# mb_1d.net
KiCad netlist of a schematic drawn in EAGLE
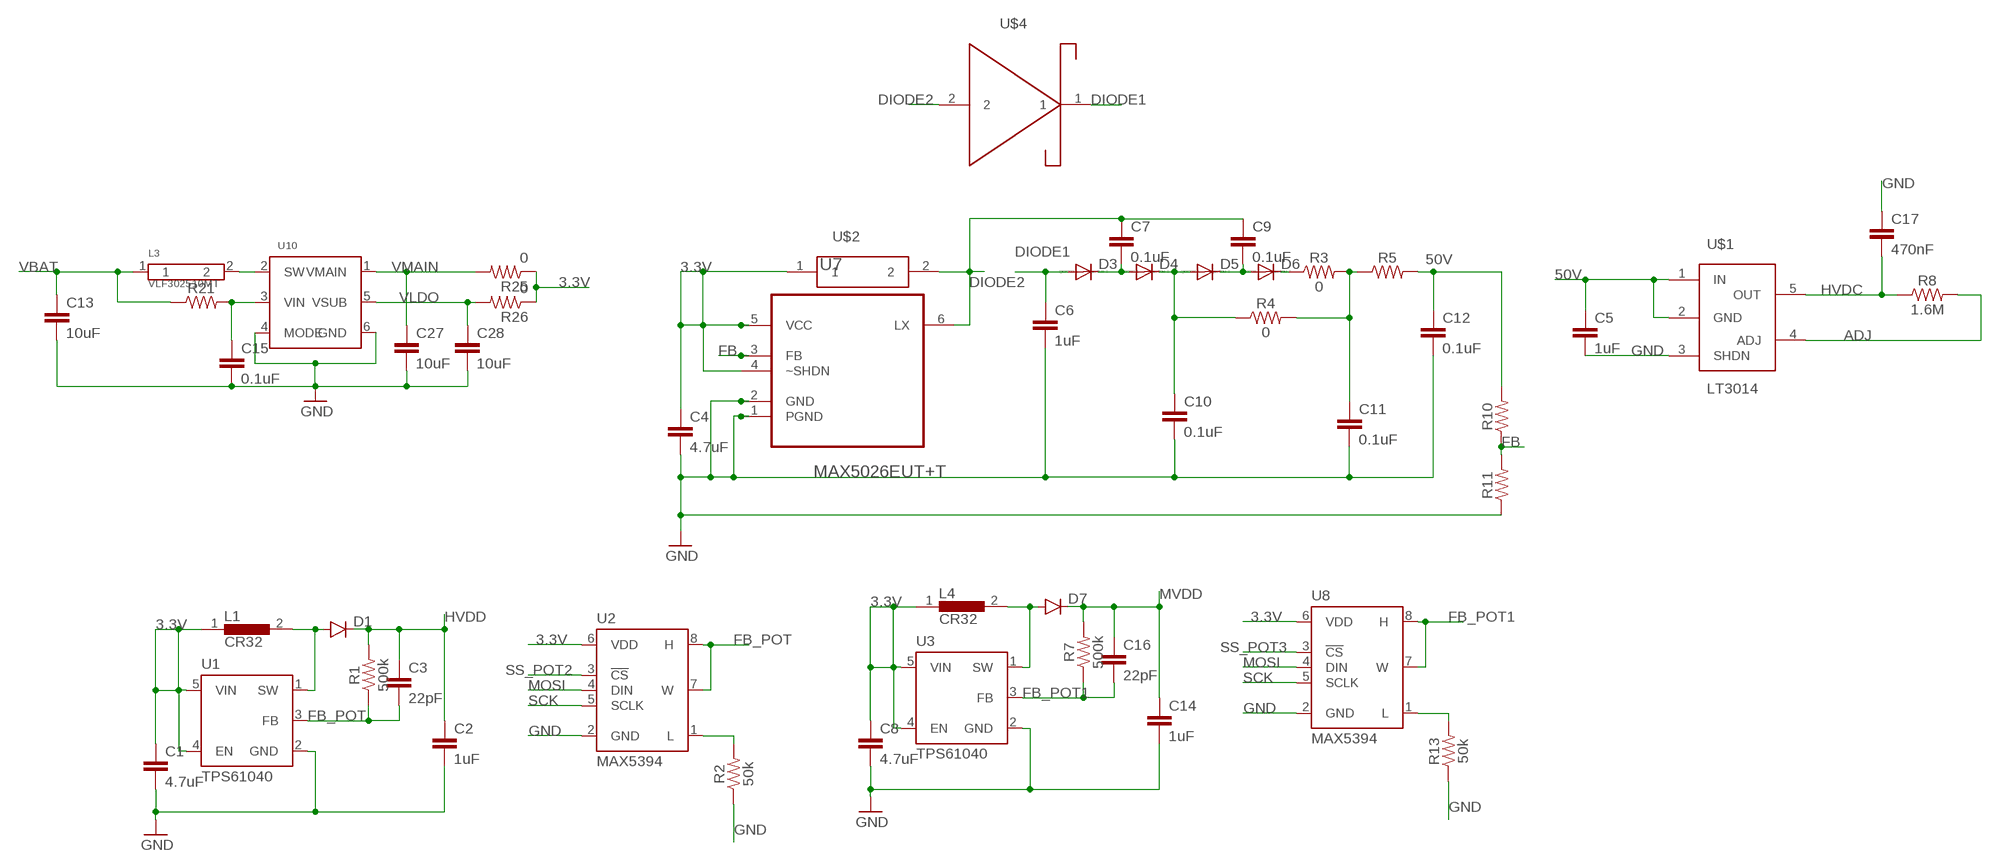
[diagram p0: schematic, sheet 1, part 1 of 2]
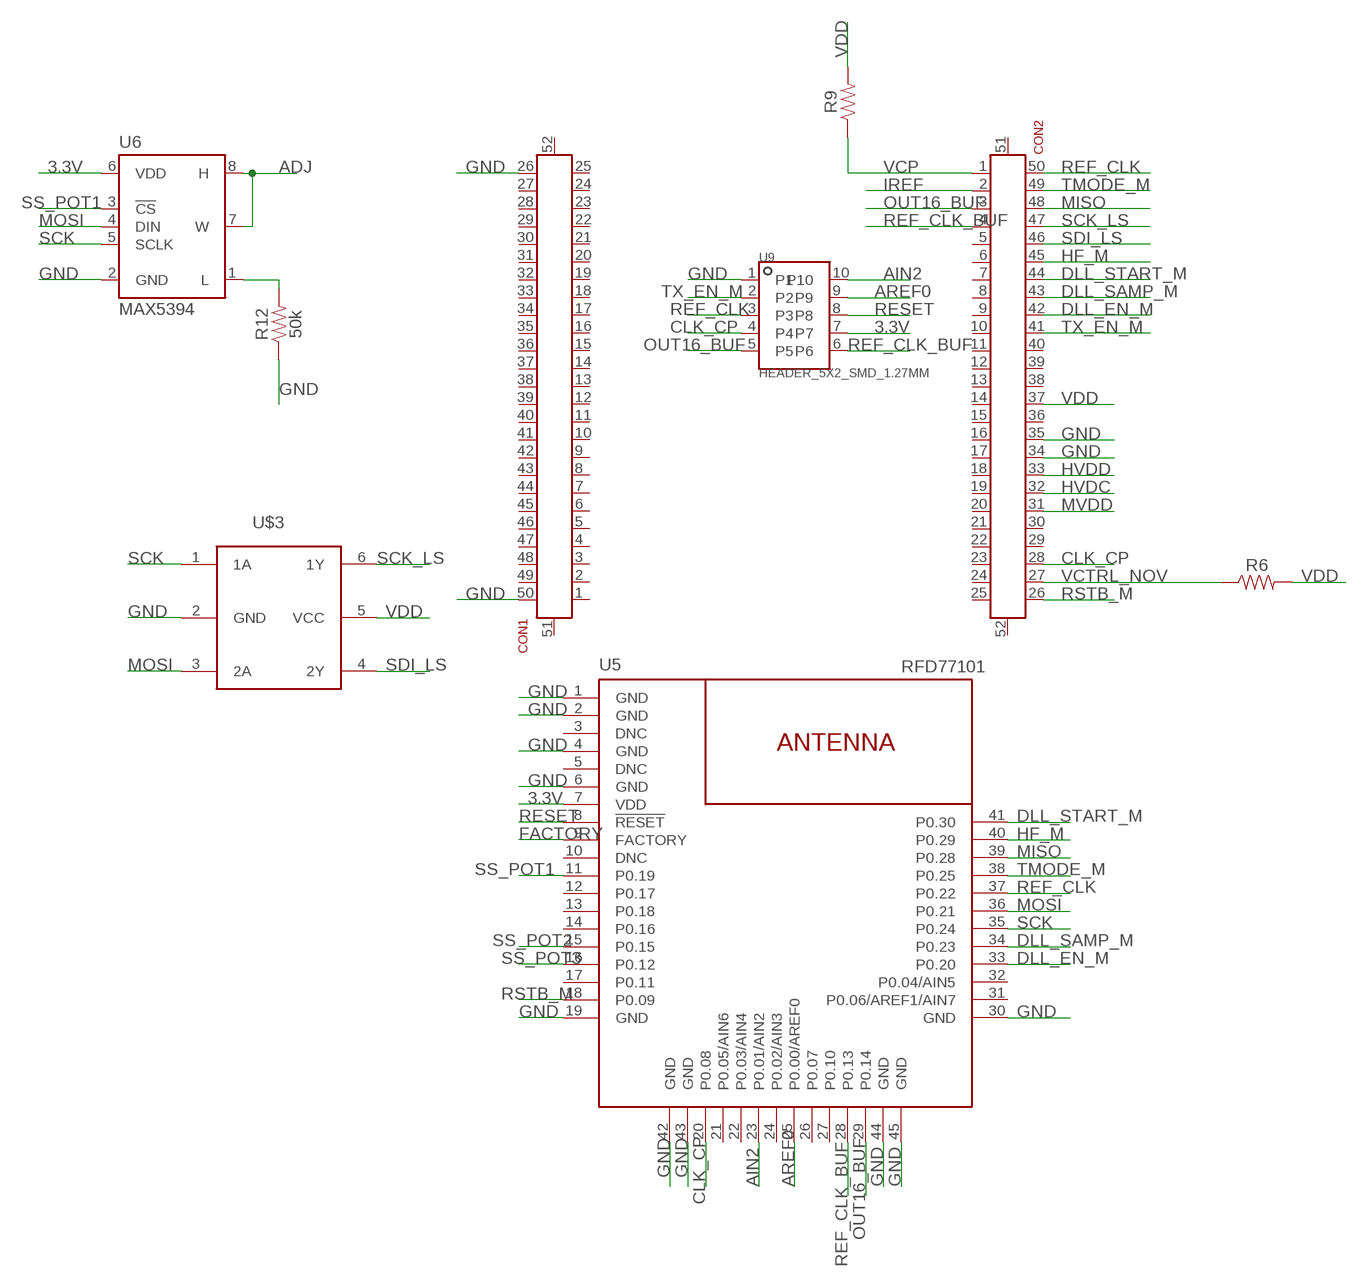
[diagram p1: schematic, sheet 1, part 2 of 2]

(export (version "E")
  (design (tool "Eeschema 10.0.6"))
  (components
    (comp (ref "C1")
      (value "4.7uF")
      (footprint "eagle-import:0805-CAP")
      (libsource (lib "eagle-import") (part "1.0UF-25V-+80/-20(0805){dblquote}"))
    )
    (comp (ref "C2")
      (value "1uF")
      (footprint "eagle-import:1206-CAP")
      (libsource (lib "eagle-import") (part "4.7UF-16V-20%,+80%-(1206)"))
    )
    (comp (ref "C3")
      (value "22pF")
      (footprint "eagle-import:0603-CAP")
      (libsource (lib "eagle-import") (part "22PF-50V-5%(0603)"))
    )
    (comp (ref "C4")
      (value "4.7uF")
      (footprint "eagle-import:0805-CAP")
      (libsource (lib "eagle-import") (part "1.0UF-25V-+80/-20(0805){dblquote}"))
    )
    (comp (ref "C5")
      (value "1uF")
      (footprint "eagle-import:1206-CAP")
      (libsource (lib "eagle-import") (part "4.7UF-16V-20%,+80%-(1206)"))
    )
    (comp (ref "C6")
      (value "1uF")
      (footprint "eagle-import:1206-CAP")
      (libsource (lib "eagle-import") (part "4.7UF-16V-20%,+80%-(1206)"))
    )
    (comp (ref "C7")
      (value "0.1uF")
      (footprint "eagle-import:0402")
      (libsource (lib "eagle-import") (part "0.1UF-0402-16V-10%"))
    )
    (comp (ref "C8")
      (value "4.7uF")
      (footprint "eagle-import:0805-CAP")
      (libsource (lib "eagle-import") (part "1.0UF-25V-+80/-20(0805){dblquote}"))
    )
    (comp (ref "C9")
      (value "0.1uF")
      (footprint "eagle-import:0402")
      (libsource (lib "eagle-import") (part "0.1UF-0402-16V-10%"))
    )
    (comp (ref "C10")
      (value "0.1uF")
      (footprint "eagle-import:0402")
      (libsource (lib "eagle-import") (part "0.1UF-0402-16V-10%"))
    )
    (comp (ref "C11")
      (value "0.1uF")
      (footprint "eagle-import:0402")
      (libsource (lib "eagle-import") (part "0.1UF-0402-16V-10%"))
    )
    (comp (ref "C12")
      (value "0.1uF")
      (footprint "eagle-import:0402")
      (libsource (lib "eagle-import") (part "0.1UF-0402-16V-10%"))
    )
    (comp (ref "C13")
      (value "10uF")
      (footprint "eagle-import:0603-CAP")
      (libsource (lib "eagle-import") (part "CAP0603-CAP"))
    )
    (comp (ref "C14")
      (value "1uF")
      (footprint "eagle-import:1206-CAP")
      (libsource (lib "eagle-import") (part "4.7UF-16V-20%,+80%-(1206)"))
    )
    (comp (ref "C15")
      (value "0.1uF")
      (footprint "eagle-import:0603-CAP")
      (libsource (lib "eagle-import") (part "CAP0603-CAP"))
    )
    (comp (ref "C16")
      (value "22pF")
      (footprint "eagle-import:0603-CAP")
      (libsource (lib "eagle-import") (part "22PF-50V-5%(0603)"))
    )
    (comp (ref "C17")
      (value "470nF")
      (footprint "eagle-import:0402")
      (libsource (lib "eagle-import") (part "470NF-0402-16V-10%"))
    )
    (comp (ref "C27")
      (value "10uF")
      (footprint "eagle-import:0603-CAP")
      (libsource (lib "eagle-import") (part "CAP0603-CAP"))
    )
    (comp (ref "C28")
      (value "10uF")
      (footprint "eagle-import:0603-CAP")
      (libsource (lib "eagle-import") (part "CAP0603-CAP"))
    )
    (comp (ref "CON1")
      (value "1013279X_AMPHENOL_2X25")
      (footprint "eagle-import:10132798-052100LF")
      (libsource (lib "eagle-import") (part "1013279X_AMPHENOL_2X25"))
    )
    (comp (ref "CON2")
      (value "1013279X_AMPHENOL_2X25")
      (footprint "eagle-import:10132798-052100LF")
      (libsource (lib "eagle-import") (part "1013279X_AMPHENOL_2X25"))
    )
    (comp (ref "D1")
      (value "DIODESOD123")
      (footprint "eagle-import:SOD-123")
      (libsource (lib "eagle-import") (part "DIODESOD123"))
    )
    (comp (ref "D3")
      (value "DIODE-SOD323-R")
      (footprint "eagle-import:SOD323-R")
      (libsource (lib "eagle-import") (part "DIODE-SOD323-R"))
    )
    (comp (ref "D4")
      (value "DIODE-SOD323-R")
      (footprint "eagle-import:SOD323-R")
      (libsource (lib "eagle-import") (part "DIODE-SOD323-R"))
    )
    (comp (ref "D5")
      (value "DIODE-SOD323-R")
      (footprint "eagle-import:SOD323-R")
      (libsource (lib "eagle-import") (part "DIODE-SOD323-R"))
    )
    (comp (ref "D6")
      (value "DIODE-SOD323-R")
      (footprint "eagle-import:SOD323-R")
      (libsource (lib "eagle-import") (part "DIODE-SOD323-R"))
    )
    (comp (ref "D7")
      (value "DIODESOD123")
      (footprint "eagle-import:SOD-123")
      (libsource (lib "eagle-import") (part "DIODESOD123"))
    )
    (comp (ref "L1")
      (value "CR32")
      (footprint "eagle-import:CR32")
      (libsource (lib "eagle-import") (part "CR32"))
    )
    (comp (ref "L3")
      (value "VLF302510MT")
      (footprint "eagle-import:VLF252010MT")
      (libsource (lib "eagle-import") (part "VLF302510MT"))
    )
    (comp (ref "L4")
      (value "CR32")
      (footprint "eagle-import:CR32")
      (libsource (lib "eagle-import") (part "CR32"))
    )
    (comp (ref "R1")
      (value "500k")
      (footprint "eagle-import:0402")
      (libsource (lib "eagle-import") (part "RESISTOR0402"))
    )
    (comp (ref "R2")
      (value "50k")
      (footprint "eagle-import:0402")
      (libsource (lib "eagle-import") (part "RESISTOR0402"))
    )
    (comp (ref "R3")
      (value "0")
      (footprint "eagle-import:0402")
      (libsource (lib "eagle-import") (part "RESISTOR0402"))
    )
    (comp (ref "R4")
      (value "0")
      (footprint "eagle-import:0402")
      (libsource (lib "eagle-import") (part "RESISTOR0402"))
    )
    (comp (ref "R5")
      (value "RESISTOR0402")
      (footprint "eagle-import:0402")
      (libsource (lib "eagle-import") (part "RESISTOR0402"))
    )
    (comp (ref "R6")
      (value "RESISTOR0402")
      (footprint "eagle-import:0402")
      (libsource (lib "eagle-import") (part "RESISTOR0402"))
    )
    (comp (ref "R7")
      (value "500k")
      (footprint "eagle-import:0402")
      (libsource (lib "eagle-import") (part "RESISTOR0402"))
    )
    (comp (ref "R8")
      (value "1.6M")
      (footprint "eagle-import:0402")
      (libsource (lib "eagle-import") (part "RESISTOR0402"))
    )
    (comp (ref "R9")
      (value "RESISTOR0402")
      (footprint "eagle-import:0402")
      (libsource (lib "eagle-import") (part "RESISTOR0402"))
    )
    (comp (ref "R10")
      (value "RESISTOR0402")
      (footprint "eagle-import:0402")
      (libsource (lib "eagle-import") (part "RESISTOR0402"))
    )
    (comp (ref "R11")
      (value "RESISTOR0402")
      (footprint "eagle-import:0402")
      (libsource (lib "eagle-import") (part "RESISTOR0402"))
    )
    (comp (ref "R12")
      (value "50k")
      (footprint "eagle-import:0402")
      (libsource (lib "eagle-import") (part "RESISTOR0402"))
    )
    (comp (ref "R13")
      (value "50k")
      (footprint "eagle-import:0402")
      (libsource (lib "eagle-import") (part "RESISTOR0402"))
    )
    (comp (ref "R21")
      (value "RESISTOR0603")
      (footprint "eagle-import:0603")
      (libsource (lib "eagle-import") (part "RESISTOR0603"))
    )
    (comp (ref "R25")
      (value "0")
      (footprint "eagle-import:0402-RES")
      (libsource (lib "eagle-import") (part "RESISTOR0402-RES"))
    )
    (comp (ref "R26")
      (value "0")
      (footprint "eagle-import:0402-RES")
      (libsource (lib "eagle-import") (part "RESISTOR0402-RES"))
    )
    (comp (ref "U$1")
      (value "LT3014")
      (footprint "eagle-import:LT3014")
      (libsource (lib "eagle-import") (part "LT3014"))
    )
    (comp (ref "U$2")
      (value "LQH3NPN470MJRL")
      (footprint "eagle-import:LQH3NPN470MJRL")
      (libsource (lib "eagle-import") (part "LQH3NPN470MJRL"))
    )
    (comp (ref "U$3")
      (value "SN74AUP2G34DCKR")
      (footprint "eagle-import:SN74AUP2G34DCKR")
      (libsource (lib "eagle-import") (part "SN74AUP2G34DCKR"))
    )
    (comp (ref "U$4")
      (value "DB2J40700L")
      (footprint "eagle-import:DB2J40700L")
      (libsource (lib "eagle-import") (part "DB2J40700L"))
    )
    (comp (ref "U1")
      (value "TPS61040")
      (footprint "eagle-import:SOT23-5")
      (libsource (lib "eagle-import") (part "TPS61040"))
    )
    (comp (ref "U2")
      (value "MAX5394")
      (footprint "eagle-import:8-TDFN-EP")
      (libsource (lib "eagle-import") (part "MAX5394"))
    )
    (comp (ref "U3")
      (value "TPS61040")
      (footprint "eagle-import:SOT23-5")
      (libsource (lib "eagle-import") (part "TPS61040"))
    )
    (comp (ref "U5")
      (value "RFD77101")
      (footprint "eagle-import:RFD77101")
      (libsource (lib "eagle-import") (part "RFD77101"))
    )
    (comp (ref "U6")
      (value "MAX5394")
      (footprint "eagle-import:8-TDFN-EP")
      (libsource (lib "eagle-import") (part "MAX5394"))
    )
    (comp (ref "U7")
      (value "MAX5026EUT+T")
      (footprint "eagle-import:SOT95P280X145-6N")
      (libsource (lib "eagle-import") (part "MAX5026EUT+T"))
    )
    (comp (ref "U8")
      (value "MAX5394")
      (footprint "eagle-import:8-TDFN-EP")
      (libsource (lib "eagle-import") (part "MAX5394"))
    )
    (comp (ref "U9")
      (value "HEADER_5X2_SMD_1.27MM")
      (footprint "eagle-import:HEADER_5X2_SMD_1.27MM")
      (libsource (lib "eagle-import") (part "HEADER_5X2_SMD_1.27MM"))
    )
    (comp (ref "U10")
      (value "TPS610981")
      (footprint "eagle-import:WSON-6")
      (libsource (lib "eagle-import") (part "TPS610981"))
    )
  )
  (nets
    (net (code "1") (name "/3.3V") (class "Default")
      (node (ref "C1") (pin "1") (pinfunction "1_1") (pintype "passive"))
      (node (ref "C4") (pin "1") (pinfunction "1_1") (pintype "passive"))
      (node (ref "C8") (pin "1") (pinfunction "1_1") (pintype "passive"))
      (node (ref "L1") (pin "1") (pinfunction "1_1") (pintype "passive"))
      (node (ref "L4") (pin "1") (pinfunction "1_1") (pintype "passive"))
      (node (ref "R25") (pin "1") (pinfunction "1_1") (pintype "passive"))
      (node (ref "R26") (pin "1") (pinfunction "1_1") (pintype "passive"))
      (node (ref "U$2") (pin "1") (pinfunction "1_1") (pintype "bidirectional"))
      (node (ref "U1") (pin "4") (pinfunction "EN_4") (pintype "input"))
      (node (ref "U1") (pin "5") (pinfunction "VIN_5") (pintype "power_in"))
      (node (ref "U2") (pin "6") (pinfunction "VDD_6") (pintype "power_in"))
      (node (ref "U3") (pin "4") (pinfunction "EN_4") (pintype "input"))
      (node (ref "U3") (pin "5") (pinfunction "VIN_5") (pintype "power_in"))
      (node (ref "U5") (pin "7") (pinfunction "VDD_7") (pintype "power_in"))
      (node (ref "U6") (pin "6") (pinfunction "VDD_6") (pintype "power_in"))
      (node (ref "U7") (pin "4") (pinfunction "~{SHDN}_4") (pintype "input"))
      (node (ref "U7") (pin "5") (pinfunction "VCC_5") (pintype "power_in"))
      (node (ref "U8") (pin "6") (pinfunction "VDD_6") (pintype "power_in"))
      (node (ref "U9") (pin "7") (pinfunction "P7_7") (pintype "bidirectional"))
    )
    (net (code "2") (name "/50V") (class "Default")
      (node (ref "C12") (pin "1") (pinfunction "1_1") (pintype "passive"))
      (node (ref "C5") (pin "1") (pinfunction "1_1") (pintype "passive"))
      (node (ref "R10") (pin "2") (pinfunction "2_2") (pintype "passive"))
      (node (ref "R5") (pin "2") (pinfunction "2_2") (pintype "passive"))
      (node (ref "U$1") (pin "1") (pinfunction "IN_1") (pintype "bidirectional"))
      (node (ref "U$1") (pin "2") (pinfunction "GND_2") (pintype "bidirectional"))
    )
    (net (code "3") (name "/ADJ") (class "Default")
      (node (ref "R8") (pin "2") (pinfunction "2_2") (pintype "passive"))
      (node (ref "U$1") (pin "4") (pinfunction "ADJ_4") (pintype "bidirectional"))
      (node (ref "U6") (pin "7") (pinfunction "W_7") (pintype "bidirectional"))
      (node (ref "U6") (pin "8") (pinfunction "H_8") (pintype "bidirectional"))
    )
    (net (code "4") (name "/AIN2") (class "Default")
      (node (ref "U5") (pin "23") (pinfunction "P0.01/AIN2_23") (pintype "bidirectional"))
      (node (ref "U9") (pin "10") (pinfunction "P10_10") (pintype "bidirectional"))
    )
    (net (code "5") (name "/AREF0") (class "Default")
      (node (ref "U5") (pin "25") (pinfunction "P0.00/AREF0_25") (pintype "bidirectional"))
      (node (ref "U9") (pin "9") (pinfunction "P9_9") (pintype "bidirectional"))
    )
    (net (code "6") (name "/CLK_CP") (class "Default")
      (node (ref "CON2") (pin "28") (pinfunction "P$28_28") (pintype "bidirectional"))
      (node (ref "U5") (pin "20") (pinfunction "P0.08_20") (pintype "bidirectional"))
      (node (ref "U9") (pin "4") (pinfunction "P4_4") (pintype "bidirectional"))
    )
    (net (code "7") (name "/DIODE1") (class "Default")
      (node (ref "C6") (pin "1") (pinfunction "1_1") (pintype "passive"))
      (node (ref "D3") (pin "A") (pinfunction "A_A") (pintype "passive"))
      (node (ref "U$4") (pin "1") (pinfunction "1_1") (pintype "bidirectional"))
    )
    (net (code "8") (name "/DIODE2") (class "Default")
      (node (ref "C7") (pin "1") (pinfunction "1_1") (pintype "passive"))
      (node (ref "C9") (pin "1") (pinfunction "1_1") (pintype "passive"))
      (node (ref "U$2") (pin "2") (pinfunction "2_2") (pintype "bidirectional"))
      (node (ref "U$4") (pin "2") (pinfunction "2_2") (pintype "bidirectional"))
      (node (ref "U7") (pin "6") (pinfunction "LX_6") (pintype "output"))
    )
    (net (code "9") (name "/DLL_EN_M") (class "Default")
      (node (ref "CON2") (pin "42") (pinfunction "P$42_42") (pintype "bidirectional"))
      (node (ref "U5") (pin "33") (pinfunction "P0.20_33") (pintype "bidirectional"))
    )
    (net (code "10") (name "/DLL_SAMP_M") (class "Default")
      (node (ref "CON2") (pin "43") (pinfunction "P$43_43") (pintype "bidirectional"))
      (node (ref "U5") (pin "34") (pinfunction "P0.23_34") (pintype "bidirectional"))
    )
    (net (code "11") (name "/DLL_START_M") (class "Default")
      (node (ref "CON2") (pin "44") (pinfunction "P$44_44") (pintype "bidirectional"))
      (node (ref "U5") (pin "41") (pinfunction "P0.30_41") (pintype "bidirectional"))
    )
    (net (code "13") (name "/FB") (class "Default")
      (node (ref "R10") (pin "1") (pinfunction "1_1") (pintype "passive"))
      (node (ref "R11") (pin "2") (pinfunction "2_2") (pintype "passive"))
      (node (ref "U7") (pin "3") (pinfunction "FB_3") (pintype "input"))
    )
    (net (code "14") (name "/FB_POT") (class "Default")
      (node (ref "C3") (pin "2") (pinfunction "2_2") (pintype "passive"))
      (node (ref "R1") (pin "1") (pinfunction "1_1") (pintype "passive"))
      (node (ref "U1") (pin "3") (pinfunction "FB_3") (pintype "bidirectional"))
      (node (ref "U2") (pin "7") (pinfunction "W_7") (pintype "bidirectional"))
      (node (ref "U2") (pin "8") (pinfunction "H_8") (pintype "bidirectional"))
    )
    (net (code "15") (name "/FB_POT1") (class "Default")
      (node (ref "C16") (pin "2") (pinfunction "2_2") (pintype "passive"))
      (node (ref "R7") (pin "1") (pinfunction "1_1") (pintype "passive"))
      (node (ref "U3") (pin "3") (pinfunction "FB_3") (pintype "bidirectional"))
      (node (ref "U8") (pin "7") (pinfunction "W_7") (pintype "bidirectional"))
      (node (ref "U8") (pin "8") (pinfunction "H_8") (pintype "bidirectional"))
    )
    (net (code "16") (name "/HF_M") (class "Default")
      (node (ref "CON2") (pin "45") (pinfunction "P$45_45") (pintype "bidirectional"))
      (node (ref "U5") (pin "40") (pinfunction "P0.29_40") (pintype "bidirectional"))
    )
    (net (code "17") (name "/HVDC") (class "Default")
      (node (ref "C17") (pin "2") (pinfunction "2_2") (pintype "passive"))
      (node (ref "CON2") (pin "32") (pinfunction "P$32_32") (pintype "bidirectional"))
      (node (ref "R8") (pin "1") (pinfunction "1_1") (pintype "passive"))
      (node (ref "U$1") (pin "5") (pinfunction "OUT_5") (pintype "bidirectional"))
    )
    (net (code "18") (name "/HVDD") (class "Default")
      (node (ref "C2") (pin "1") (pinfunction "1_1") (pintype "passive"))
      (node (ref "C3") (pin "1") (pinfunction "1_1") (pintype "passive"))
      (node (ref "CON2") (pin "33") (pinfunction "P$33_33") (pintype "bidirectional"))
      (node (ref "D1") (pin "C") (pinfunction "C_C") (pintype "passive"))
      (node (ref "R1") (pin "2") (pinfunction "2_2") (pintype "passive"))
    )
    (net (code "19") (name "/IREF") (class "Default")
      (node (ref "CON2") (pin "2") (pinfunction "P$2_2") (pintype "bidirectional"))
    )
    (net (code "20") (name "/MISO") (class "Default")
      (node (ref "CON2") (pin "48") (pinfunction "P$48_48") (pintype "bidirectional"))
      (node (ref "U5") (pin "39") (pinfunction "P0.28_39") (pintype "bidirectional"))
    )
    (net (code "21") (name "/MOSI") (class "Default")
      (node (ref "U$3") (pin "3") (pinfunction "2A_3") (pintype "bidirectional"))
      (node (ref "U2") (pin "4") (pinfunction "DIN_4") (pintype "input"))
      (node (ref "U5") (pin "36") (pinfunction "P0.21_36") (pintype "bidirectional"))
      (node (ref "U6") (pin "4") (pinfunction "DIN_4") (pintype "input"))
      (node (ref "U8") (pin "4") (pinfunction "DIN_4") (pintype "input"))
    )
    (net (code "22") (name "/MVDD") (class "Default")
      (node (ref "C14") (pin "1") (pinfunction "1_1") (pintype "passive"))
      (node (ref "C16") (pin "1") (pinfunction "1_1") (pintype "passive"))
      (node (ref "CON2") (pin "31") (pinfunction "P$31_31") (pintype "bidirectional"))
      (node (ref "D7") (pin "C") (pinfunction "C_C") (pintype "passive"))
      (node (ref "R7") (pin "2") (pinfunction "2_2") (pintype "passive"))
    )
    (net (code "23") (name "/OUT16_BUF") (class "Default")
      (node (ref "CON2") (pin "3") (pinfunction "P$3_3") (pintype "bidirectional"))
      (node (ref "U5") (pin "29") (pinfunction "P0.14_29") (pintype "bidirectional"))
      (node (ref "U9") (pin "5") (pinfunction "P5_5") (pintype "bidirectional"))
    )
    (net (code "24") (name "/REF_CLK") (class "Default")
      (node (ref "CON2") (pin "50") (pinfunction "P$50_50") (pintype "bidirectional"))
      (node (ref "U5") (pin "37") (pinfunction "P0.22_37") (pintype "bidirectional"))
      (node (ref "U9") (pin "3") (pinfunction "P3_3") (pintype "bidirectional"))
    )
    (net (code "25") (name "/REF_CLK_BUF") (class "Default")
      (node (ref "CON2") (pin "4") (pinfunction "P$4_4") (pintype "bidirectional"))
      (node (ref "U5") (pin "28") (pinfunction "P0.13_28") (pintype "bidirectional"))
      (node (ref "U9") (pin "6") (pinfunction "P6_6") (pintype "bidirectional"))
    )
    (net (code "26") (name "/RESET") (class "Default")
      (node (ref "U5") (pin "8") (pinfunction "~{RESET}_8") (pintype "input"))
      (node (ref "U9") (pin "8") (pinfunction "P8_8") (pintype "bidirectional"))
    )
    (net (code "27") (name "/RSTB_M") (class "Default")
      (node (ref "CON2") (pin "26") (pinfunction "P$26_26") (pintype "bidirectional"))
      (node (ref "U5") (pin "18") (pinfunction "P0.09_18") (pintype "bidirectional"))
    )
    (net (code "28") (name "/SCK") (class "Default")
      (node (ref "U$3") (pin "1") (pinfunction "1A_1") (pintype "bidirectional"))
      (node (ref "U2") (pin "5") (pinfunction "SCLK_5") (pintype "input"))
      (node (ref "U5") (pin "35") (pinfunction "P0.24_35") (pintype "bidirectional"))
      (node (ref "U6") (pin "5") (pinfunction "SCLK_5") (pintype "input"))
      (node (ref "U8") (pin "5") (pinfunction "SCLK_5") (pintype "input"))
    )
    (net (code "29") (name "/SCK_LS") (class "Default")
      (node (ref "CON2") (pin "47") (pinfunction "P$47_47") (pintype "bidirectional"))
      (node (ref "U$3") (pin "6") (pinfunction "1Y_6") (pintype "bidirectional"))
    )
    (net (code "30") (name "/SDI_LS") (class "Default")
      (node (ref "CON2") (pin "46") (pinfunction "P$46_46") (pintype "bidirectional"))
      (node (ref "U$3") (pin "4") (pinfunction "2Y_4") (pintype "bidirectional"))
    )
    (net (code "31") (name "/SS_POT1") (class "Default")
      (node (ref "U5") (pin "11") (pinfunction "P0.19_11") (pintype "bidirectional"))
      (node (ref "U6") (pin "3") (pinfunction "~{CS}_3") (pintype "input"))
    )
    (net (code "32") (name "/SS_POT2") (class "Default")
      (node (ref "U2") (pin "3") (pinfunction "~{CS}_3") (pintype "input"))
      (node (ref "U5") (pin "15") (pinfunction "P0.15_15") (pintype "bidirectional"))
    )
    (net (code "33") (name "/SS_POT3") (class "Default")
      (node (ref "U5") (pin "16") (pinfunction "P0.12_16") (pintype "bidirectional"))
      (node (ref "U8") (pin "3") (pinfunction "~{CS}_3") (pintype "input"))
    )
    (net (code "34") (name "/TMODE_M") (class "Default")
      (node (ref "CON2") (pin "49") (pinfunction "P$49_49") (pintype "bidirectional"))
      (node (ref "U5") (pin "38") (pinfunction "P0.25_38") (pintype "bidirectional"))
    )
    (net (code "35") (name "/TX_EN_M") (class "Default")
      (node (ref "CON2") (pin "41") (pinfunction "P$41_41") (pintype "bidirectional"))
      (node (ref "U9") (pin "2") (pinfunction "P2_2") (pintype "bidirectional"))
    )
    (net (code "36") (name "/VBAT") (class "Default")
      (node (ref "C13") (pin "1") (pinfunction "1_1") (pintype "passive"))
      (node (ref "L3") (pin "1") (pinfunction "1_1") (pintype "bidirectional"))
      (node (ref "R21") (pin "1") (pinfunction "1_1") (pintype "passive"))
    )
    (net (code "37") (name "/VCP") (class "Default")
      (node (ref "CON2") (pin "1") (pinfunction "P$1_1") (pintype "bidirectional"))
      (node (ref "R9") (pin "1") (pinfunction "1_1") (pintype "passive"))
    )
    (net (code "38") (name "/VCTRL_NOV") (class "Default")
      (node (ref "CON2") (pin "27") (pinfunction "P$27_27") (pintype "bidirectional"))
      (node (ref "R6") (pin "1") (pinfunction "1_1") (pintype "passive"))
    )
    (net (code "39") (name "/VDD") (class "Default")
      (node (ref "CON2") (pin "37") (pinfunction "P$37_37") (pintype "bidirectional"))
      (node (ref "R6") (pin "2") (pinfunction "2_2") (pintype "passive"))
      (node (ref "R9") (pin "2") (pinfunction "2_2") (pintype "passive"))
      (node (ref "U$3") (pin "5") (pinfunction "VCC_5") (pintype "bidirectional"))
    )
    (net (code "40") (name "/VLDO") (class "Default")
      (node (ref "C28") (pin "1") (pinfunction "1_1") (pintype "passive"))
      (node (ref "R26") (pin "2") (pinfunction "2_2") (pintype "passive"))
      (node (ref "U10") (pin "5") (pinfunction "VSUB_5") (pintype "bidirectional"))
    )
    (net (code "41") (name "/VMAIN") (class "Default")
      (node (ref "C27") (pin "1") (pinfunction "1_1") (pintype "passive"))
      (node (ref "R25") (pin "2") (pinfunction "2_2") (pintype "passive"))
      (node (ref "U10") (pin "1") (pinfunction "VMAIN_1") (pintype "bidirectional"))
    )
    (net (code "42") (name "GND") (class "Default")
      (node (ref "C1") (pin "2") (pinfunction "2_2") (pintype "passive"))
      (node (ref "C10") (pin "2") (pinfunction "2_2") (pintype "passive"))
      (node (ref "C11") (pin "2") (pinfunction "2_2") (pintype "passive"))
      (node (ref "C12") (pin "2") (pinfunction "2_2") (pintype "passive"))
      (node (ref "C13") (pin "2") (pinfunction "2_2") (pintype "passive"))
      (node (ref "C14") (pin "2") (pinfunction "2_2") (pintype "passive"))
      (node (ref "C15") (pin "2") (pinfunction "2_2") (pintype "passive"))
      (node (ref "C17") (pin "1") (pinfunction "1_1") (pintype "passive"))
      (node (ref "C2") (pin "2") (pinfunction "2_2") (pintype "passive"))
      (node (ref "C27") (pin "2") (pinfunction "2_2") (pintype "passive"))
      (node (ref "C28") (pin "2") (pinfunction "2_2") (pintype "passive"))
      (node (ref "C4") (pin "2") (pinfunction "2_2") (pintype "passive"))
      (node (ref "C5") (pin "2") (pinfunction "2_2") (pintype "passive"))
      (node (ref "C6") (pin "2") (pinfunction "2_2") (pintype "passive"))
      (node (ref "C8") (pin "2") (pinfunction "2_2") (pintype "passive"))
      (node (ref "CON1") (pin "26") (pinfunction "P$26_26") (pintype "bidirectional"))
      (node (ref "CON1") (pin "50") (pinfunction "P$50_50") (pintype "bidirectional"))
      (node (ref "CON2") (pin "34") (pinfunction "P$34_34") (pintype "bidirectional"))
      (node (ref "CON2") (pin "35") (pinfunction "P$35_35") (pintype "bidirectional"))
      (node (ref "R11") (pin "1") (pinfunction "1_1") (pintype "passive"))
      (node (ref "R12") (pin "1") (pinfunction "1_1") (pintype "passive"))
      (node (ref "R13") (pin "1") (pinfunction "1_1") (pintype "passive"))
      (node (ref "R2") (pin "1") (pinfunction "1_1") (pintype "passive"))
      (node (ref "U$1") (pin "3") (pinfunction "SHDN_3") (pintype "bidirectional"))
      (node (ref "U$3") (pin "2") (pinfunction "GND_2") (pintype "bidirectional"))
      (node (ref "U1") (pin "2") (pinfunction "GND_2") (pintype "power_in"))
      (node (ref "U10") (pin "4") (pinfunction "MODE_4") (pintype "bidirectional"))
      (node (ref "U10") (pin "6") (pinfunction "GND_6") (pintype "bidirectional"))
      (node (ref "U2") (pin "2") (pinfunction "GND_2") (pintype "power_in"))
      (node (ref "U3") (pin "2") (pinfunction "GND_2") (pintype "power_in"))
      (node (ref "U5") (pin "1") (pinfunction "GND_1") (pintype "power_in"))
      (node (ref "U5") (pin "19") (pinfunction "GND_19") (pintype "power_in"))
      (node (ref "U5") (pin "2") (pinfunction "GND_2") (pintype "power_in"))
      (node (ref "U5") (pin "30") (pinfunction "GND_30") (pintype "power_in"))
      (node (ref "U5") (pin "4") (pinfunction "GND_4") (pintype "power_in"))
      (node (ref "U5") (pin "42") (pinfunction "GND_42") (pintype "power_in"))
      (node (ref "U5") (pin "43") (pinfunction "GND_43") (pintype "power_in"))
      (node (ref "U5") (pin "44") (pinfunction "GND_44") (pintype "power_in"))
      (node (ref "U5") (pin "45") (pinfunction "GND_45") (pintype "power_in"))
      (node (ref "U5") (pin "6") (pinfunction "GND_6") (pintype "power_in"))
      (node (ref "U6") (pin "2") (pinfunction "GND_2") (pintype "power_in"))
      (node (ref "U7") (pin "1") (pinfunction "PGND_1") (pintype "passive"))
      (node (ref "U7") (pin "2") (pinfunction "GND_2") (pintype "passive"))
      (node (ref "U8") (pin "2") (pinfunction "GND_2") (pintype "power_in"))
      (node (ref "U9") (pin "1") (pinfunction "P1_1") (pintype "bidirectional"))
    )
    (net (code "43") (name "Net-(C7-Pad2)") (class "Default")
      (node (ref "C7") (pin "2") (pinfunction "2_2") (pintype "passive"))
      (node (ref "D3") (pin "C") (pinfunction "C_C") (pintype "passive"))
      (node (ref "D4") (pin "A") (pinfunction "A_A") (pintype "passive"))
    )
    (net (code "44") (name "Net-(C9-Pad2)") (class "Default")
      (node (ref "C9") (pin "2") (pinfunction "2_2") (pintype "passive"))
      (node (ref "D5") (pin "C") (pinfunction "C_C") (pintype "passive"))
      (node (ref "D6") (pin "A") (pinfunction "A_A") (pintype "passive"))
    )
    (net (code "45") (name "Net-(C10-Pad1)") (class "Default")
      (node (ref "C10") (pin "1") (pinfunction "1_1") (pintype "passive"))
      (node (ref "D4") (pin "C") (pinfunction "C_C") (pintype "passive"))
      (node (ref "D5") (pin "A") (pinfunction "A_A") (pintype "passive"))
      (node (ref "R4") (pin "1") (pinfunction "1_1") (pintype "passive"))
    )
    (net (code "46") (name "Net-(C11-Pad1)") (class "Default")
      (node (ref "C11") (pin "1") (pinfunction "1_1") (pintype "passive"))
      (node (ref "R3") (pin "2") (pinfunction "2_2") (pintype "passive"))
      (node (ref "R4") (pin "2") (pinfunction "2_2") (pintype "passive"))
      (node (ref "R5") (pin "1") (pinfunction "1_1") (pintype "passive"))
    )
    (net (code "47") (name "Net-(D6-PadC)") (class "Default")
      (node (ref "D6") (pin "C") (pinfunction "C_C") (pintype "passive"))
      (node (ref "R3") (pin "1") (pinfunction "1_1") (pintype "passive"))
    )
    (net (code "48") (name "Net-(U1-SW)") (class "Default")
      (node (ref "D1") (pin "A") (pinfunction "A_A") (pintype "passive"))
      (node (ref "L1") (pin "2") (pinfunction "2_2") (pintype "passive"))
      (node (ref "U1") (pin "1") (pinfunction "SW_1") (pintype "bidirectional"))
    )
    (net (code "49") (name "Net-(U2-L)") (class "Default")
      (node (ref "R2") (pin "2") (pinfunction "2_2") (pintype "passive"))
      (node (ref "U2") (pin "1") (pinfunction "L_1") (pintype "bidirectional"))
    )
    (net (code "50") (name "Net-(U3-SW)") (class "Default")
      (node (ref "D7") (pin "A") (pinfunction "A_A") (pintype "passive"))
      (node (ref "L4") (pin "2") (pinfunction "2_2") (pintype "passive"))
      (node (ref "U3") (pin "1") (pinfunction "SW_1") (pintype "bidirectional"))
    )
    (net (code "51") (name "Net-(U6-L)") (class "Default")
      (node (ref "R12") (pin "2") (pinfunction "2_2") (pintype "passive"))
      (node (ref "U6") (pin "1") (pinfunction "L_1") (pintype "bidirectional"))
    )
    (net (code "52") (name "Net-(U8-L)") (class "Default")
      (node (ref "R13") (pin "2") (pinfunction "2_2") (pintype "passive"))
      (node (ref "U8") (pin "1") (pinfunction "L_1") (pintype "bidirectional"))
    )
    (net (code "53") (name "Net-(U10-SW)") (class "Default")
      (node (ref "L3") (pin "2") (pinfunction "2_2") (pintype "bidirectional"))
      (node (ref "U10") (pin "2") (pinfunction "SW_2") (pintype "bidirectional"))
    )
    (net (code "54") (name "Net-(U10-VIN)") (class "Default")
      (node (ref "C15") (pin "1") (pinfunction "1_1") (pintype "passive"))
      (node (ref "R21") (pin "2") (pinfunction "2_2") (pintype "passive"))
      (node (ref "U10") (pin "3") (pinfunction "VIN_3") (pintype "bidirectional"))
    )
    (net (code "55") (name "unconnected-(CON1-P$1-Pad1)") (class "Default")
      (node (ref "CON1") (pin "1") (pinfunction "P$1_1") (pintype "bidirectional"))
    )
    (net (code "56") (name "unconnected-(CON1-P$2-Pad2)") (class "Default")
      (node (ref "CON1") (pin "2") (pinfunction "P$2_2") (pintype "bidirectional"))
    )
    (net (code "57") (name "unconnected-(CON1-P$3-Pad3)") (class "Default")
      (node (ref "CON1") (pin "3") (pinfunction "P$3_3") (pintype "bidirectional"))
    )
    (net (code "58") (name "unconnected-(CON1-P$4-Pad4)") (class "Default")
      (node (ref "CON1") (pin "4") (pinfunction "P$4_4") (pintype "bidirectional"))
    )
    (net (code "59") (name "unconnected-(CON1-P$5-Pad5)") (class "Default")
      (node (ref "CON1") (pin "5") (pinfunction "P$5_5") (pintype "bidirectional"))
    )
    (net (code "60") (name "unconnected-(CON1-P$6-Pad6)") (class "Default")
      (node (ref "CON1") (pin "6") (pinfunction "P$6_6") (pintype "bidirectional"))
    )
    (net (code "61") (name "unconnected-(CON1-P$7-Pad7)") (class "Default")
      (node (ref "CON1") (pin "7") (pinfunction "P$7_7") (pintype "bidirectional"))
    )
    (net (code "62") (name "unconnected-(CON1-P$8-Pad8)") (class "Default")
      (node (ref "CON1") (pin "8") (pinfunction "P$8_8") (pintype "bidirectional"))
    )
    (net (code "63") (name "unconnected-(CON1-P$9-Pad9)") (class "Default")
      (node (ref "CON1") (pin "9") (pinfunction "P$9_9") (pintype "bidirectional"))
    )
    (net (code "64") (name "unconnected-(CON1-P$10-Pad10)") (class "Default")
      (node (ref "CON1") (pin "10") (pinfunction "P$10_10") (pintype "bidirectional"))
    )
    (net (code "65") (name "unconnected-(CON1-P$11-Pad11)") (class "Default")
      (node (ref "CON1") (pin "11") (pinfunction "P$11_11") (pintype "bidirectional"))
    )
    (net (code "66") (name "unconnected-(CON1-P$12-Pad12)") (class "Default")
      (node (ref "CON1") (pin "12") (pinfunction "P$12_12") (pintype "bidirectional"))
    )
    (net (code "67") (name "unconnected-(CON1-P$13-Pad13)") (class "Default")
      (node (ref "CON1") (pin "13") (pinfunction "P$13_13") (pintype "bidirectional"))
    )
    (net (code "68") (name "unconnected-(CON1-P$14-Pad14)") (class "Default")
      (node (ref "CON1") (pin "14") (pinfunction "P$14_14") (pintype "bidirectional"))
    )
    (net (code "69") (name "unconnected-(CON1-P$15-Pad15)") (class "Default")
      (node (ref "CON1") (pin "15") (pinfunction "P$15_15") (pintype "bidirectional"))
    )
    (net (code "70") (name "unconnected-(CON1-P$16-Pad16)") (class "Default")
      (node (ref "CON1") (pin "16") (pinfunction "P$16_16") (pintype "bidirectional"))
    )
    (net (code "71") (name "unconnected-(CON1-P$17-Pad17)") (class "Default")
      (node (ref "CON1") (pin "17") (pinfunction "P$17_17") (pintype "bidirectional"))
    )
    (net (code "72") (name "unconnected-(CON1-P$18-Pad18)") (class "Default")
      (node (ref "CON1") (pin "18") (pinfunction "P$18_18") (pintype "bidirectional"))
    )
    (net (code "73") (name "unconnected-(CON1-P$19-Pad19)") (class "Default")
      (node (ref "CON1") (pin "19") (pinfunction "P$19_19") (pintype "bidirectional"))
    )
    (net (code "74") (name "unconnected-(CON1-P$20-Pad20)") (class "Default")
      (node (ref "CON1") (pin "20") (pinfunction "P$20_20") (pintype "bidirectional"))
    )
    (net (code "75") (name "unconnected-(CON1-P$21-Pad21)") (class "Default")
      (node (ref "CON1") (pin "21") (pinfunction "P$21_21") (pintype "bidirectional"))
    )
    (net (code "76") (name "unconnected-(CON1-P$22-Pad22)") (class "Default")
      (node (ref "CON1") (pin "22") (pinfunction "P$22_22") (pintype "bidirectional"))
    )
    (net (code "77") (name "unconnected-(CON1-P$23-Pad23)") (class "Default")
      (node (ref "CON1") (pin "23") (pinfunction "P$23_23") (pintype "bidirectional"))
    )
    (net (code "78") (name "unconnected-(CON1-P$24-Pad24)") (class "Default")
      (node (ref "CON1") (pin "24") (pinfunction "P$24_24") (pintype "bidirectional"))
    )
    (net (code "79") (name "unconnected-(CON1-P$25-Pad25)") (class "Default")
      (node (ref "CON1") (pin "25") (pinfunction "P$25_25") (pintype "bidirectional"))
    )
    (net (code "80") (name "unconnected-(CON1-P$27-Pad27)") (class "Default")
      (node (ref "CON1") (pin "27") (pinfunction "P$27_27") (pintype "bidirectional"))
    )
    (net (code "81") (name "unconnected-(CON1-P$28-Pad28)") (class "Default")
      (node (ref "CON1") (pin "28") (pinfunction "P$28_28") (pintype "bidirectional"))
    )
    (net (code "82") (name "unconnected-(CON1-P$29-Pad29)") (class "Default")
      (node (ref "CON1") (pin "29") (pinfunction "P$29_29") (pintype "bidirectional"))
    )
    (net (code "83") (name "unconnected-(CON1-P$30-Pad30)") (class "Default")
      (node (ref "CON1") (pin "30") (pinfunction "P$30_30") (pintype "bidirectional"))
    )
    (net (code "84") (name "unconnected-(CON1-P$31-Pad31)") (class "Default")
      (node (ref "CON1") (pin "31") (pinfunction "P$31_31") (pintype "bidirectional"))
    )
    (net (code "85") (name "unconnected-(CON1-P$32-Pad32)") (class "Default")
      (node (ref "CON1") (pin "32") (pinfunction "P$32_32") (pintype "bidirectional"))
    )
    (net (code "86") (name "unconnected-(CON1-P$33-Pad33)") (class "Default")
      (node (ref "CON1") (pin "33") (pinfunction "P$33_33") (pintype "bidirectional"))
    )
    (net (code "87") (name "unconnected-(CON1-P$34-Pad34)") (class "Default")
      (node (ref "CON1") (pin "34") (pinfunction "P$34_34") (pintype "bidirectional"))
    )
    (net (code "88") (name "unconnected-(CON1-P$35-Pad35)") (class "Default")
      (node (ref "CON1") (pin "35") (pinfunction "P$35_35") (pintype "bidirectional"))
    )
    (net (code "89") (name "unconnected-(CON1-P$36-Pad36)") (class "Default")
      (node (ref "CON1") (pin "36") (pinfunction "P$36_36") (pintype "bidirectional"))
    )
    (net (code "90") (name "unconnected-(CON1-P$37-Pad37)") (class "Default")
      (node (ref "CON1") (pin "37") (pinfunction "P$37_37") (pintype "bidirectional"))
    )
    (net (code "91") (name "unconnected-(CON1-P$38-Pad38)") (class "Default")
      (node (ref "CON1") (pin "38") (pinfunction "P$38_38") (pintype "bidirectional"))
    )
    (net (code "92") (name "unconnected-(CON1-P$39-Pad39)") (class "Default")
      (node (ref "CON1") (pin "39") (pinfunction "P$39_39") (pintype "bidirectional"))
    )
    (net (code "93") (name "unconnected-(CON1-P$40-Pad40)") (class "Default")
      (node (ref "CON1") (pin "40") (pinfunction "P$40_40") (pintype "bidirectional"))
    )
    (net (code "94") (name "unconnected-(CON1-P$41-Pad41)") (class "Default")
      (node (ref "CON1") (pin "41") (pinfunction "P$41_41") (pintype "bidirectional"))
    )
    (net (code "95") (name "unconnected-(CON1-P$42-Pad42)") (class "Default")
      (node (ref "CON1") (pin "42") (pinfunction "P$42_42") (pintype "bidirectional"))
    )
    (net (code "96") (name "unconnected-(CON1-P$43-Pad43)") (class "Default")
      (node (ref "CON1") (pin "43") (pinfunction "P$43_43") (pintype "bidirectional"))
    )
    (net (code "97") (name "unconnected-(CON1-P$44-Pad44)") (class "Default")
      (node (ref "CON1") (pin "44") (pinfunction "P$44_44") (pintype "bidirectional"))
    )
    (net (code "98") (name "unconnected-(CON1-P$45-Pad45)") (class "Default")
      (node (ref "CON1") (pin "45") (pinfunction "P$45_45") (pintype "bidirectional"))
    )
    (net (code "99") (name "unconnected-(CON1-P$46-Pad46)") (class "Default")
      (node (ref "CON1") (pin "46") (pinfunction "P$46_46") (pintype "bidirectional"))
    )
    (net (code "100") (name "unconnected-(CON1-P$47-Pad47)") (class "Default")
      (node (ref "CON1") (pin "47") (pinfunction "P$47_47") (pintype "bidirectional"))
    )
    (net (code "101") (name "unconnected-(CON1-P$48-Pad48)") (class "Default")
      (node (ref "CON1") (pin "48") (pinfunction "P$48_48") (pintype "bidirectional"))
    )
    (net (code "102") (name "unconnected-(CON1-P$49-Pad49)") (class "Default")
      (node (ref "CON1") (pin "49") (pinfunction "P$49_49") (pintype "bidirectional"))
    )
    (net (code "103") (name "unconnected-(CON1-P$51-Pad51)") (class "Default")
      (node (ref "CON1") (pin "51") (pinfunction "P$51_51") (pintype "bidirectional"))
    )
    (net (code "104") (name "unconnected-(CON1-P$52-Pad52)") (class "Default")
      (node (ref "CON1") (pin "52") (pinfunction "P$52_52") (pintype "bidirectional"))
    )
    (net (code "105") (name "unconnected-(CON2-P$5-Pad5)") (class "Default")
      (node (ref "CON2") (pin "5") (pinfunction "P$5_5") (pintype "bidirectional"))
    )
    (net (code "106") (name "unconnected-(CON2-P$6-Pad6)") (class "Default")
      (node (ref "CON2") (pin "6") (pinfunction "P$6_6") (pintype "bidirectional"))
    )
    (net (code "107") (name "unconnected-(CON2-P$7-Pad7)") (class "Default")
      (node (ref "CON2") (pin "7") (pinfunction "P$7_7") (pintype "bidirectional"))
    )
    (net (code "108") (name "unconnected-(CON2-P$8-Pad8)") (class "Default")
      (node (ref "CON2") (pin "8") (pinfunction "P$8_8") (pintype "bidirectional"))
    )
    (net (code "109") (name "unconnected-(CON2-P$9-Pad9)") (class "Default")
      (node (ref "CON2") (pin "9") (pinfunction "P$9_9") (pintype "bidirectional"))
    )
    (net (code "110") (name "unconnected-(CON2-P$10-Pad10)") (class "Default")
      (node (ref "CON2") (pin "10") (pinfunction "P$10_10") (pintype "bidirectional"))
    )
    (net (code "111") (name "unconnected-(CON2-P$11-Pad11)") (class "Default")
      (node (ref "CON2") (pin "11") (pinfunction "P$11_11") (pintype "bidirectional"))
    )
    (net (code "112") (name "unconnected-(CON2-P$12-Pad12)") (class "Default")
      (node (ref "CON2") (pin "12") (pinfunction "P$12_12") (pintype "bidirectional"))
    )
    (net (code "113") (name "unconnected-(CON2-P$13-Pad13)") (class "Default")
      (node (ref "CON2") (pin "13") (pinfunction "P$13_13") (pintype "bidirectional"))
    )
    (net (code "114") (name "unconnected-(CON2-P$14-Pad14)") (class "Default")
      (node (ref "CON2") (pin "14") (pinfunction "P$14_14") (pintype "bidirectional"))
    )
    (net (code "115") (name "unconnected-(CON2-P$15-Pad15)") (class "Default")
      (node (ref "CON2") (pin "15") (pinfunction "P$15_15") (pintype "bidirectional"))
    )
    (net (code "116") (name "unconnected-(CON2-P$16-Pad16)") (class "Default")
      (node (ref "CON2") (pin "16") (pinfunction "P$16_16") (pintype "bidirectional"))
    )
    (net (code "117") (name "unconnected-(CON2-P$17-Pad17)") (class "Default")
      (node (ref "CON2") (pin "17") (pinfunction "P$17_17") (pintype "bidirectional"))
    )
    (net (code "118") (name "unconnected-(CON2-P$18-Pad18)") (class "Default")
      (node (ref "CON2") (pin "18") (pinfunction "P$18_18") (pintype "bidirectional"))
    )
    (net (code "119") (name "unconnected-(CON2-P$19-Pad19)") (class "Default")
      (node (ref "CON2") (pin "19") (pinfunction "P$19_19") (pintype "bidirectional"))
    )
    (net (code "120") (name "unconnected-(CON2-P$20-Pad20)") (class "Default")
      (node (ref "CON2") (pin "20") (pinfunction "P$20_20") (pintype "bidirectional"))
    )
    (net (code "121") (name "unconnected-(CON2-P$21-Pad21)") (class "Default")
      (node (ref "CON2") (pin "21") (pinfunction "P$21_21") (pintype "bidirectional"))
    )
    (net (code "122") (name "unconnected-(CON2-P$22-Pad22)") (class "Default")
      (node (ref "CON2") (pin "22") (pinfunction "P$22_22") (pintype "bidirectional"))
    )
    (net (code "123") (name "unconnected-(CON2-P$23-Pad23)") (class "Default")
      (node (ref "CON2") (pin "23") (pinfunction "P$23_23") (pintype "bidirectional"))
    )
    (net (code "124") (name "unconnected-(CON2-P$24-Pad24)") (class "Default")
      (node (ref "CON2") (pin "24") (pinfunction "P$24_24") (pintype "bidirectional"))
    )
    (net (code "125") (name "unconnected-(CON2-P$25-Pad25)") (class "Default")
      (node (ref "CON2") (pin "25") (pinfunction "P$25_25") (pintype "bidirectional"))
    )
    (net (code "126") (name "unconnected-(CON2-P$29-Pad29)") (class "Default")
      (node (ref "CON2") (pin "29") (pinfunction "P$29_29") (pintype "bidirectional"))
    )
    (net (code "127") (name "unconnected-(CON2-P$30-Pad30)") (class "Default")
      (node (ref "CON2") (pin "30") (pinfunction "P$30_30") (pintype "bidirectional"))
    )
    (net (code "128") (name "unconnected-(CON2-P$36-Pad36)") (class "Default")
      (node (ref "CON2") (pin "36") (pinfunction "P$36_36") (pintype "bidirectional"))
    )
    (net (code "129") (name "unconnected-(CON2-P$38-Pad38)") (class "Default")
      (node (ref "CON2") (pin "38") (pinfunction "P$38_38") (pintype "bidirectional"))
    )
    (net (code "130") (name "unconnected-(CON2-P$39-Pad39)") (class "Default")
      (node (ref "CON2") (pin "39") (pinfunction "P$39_39") (pintype "bidirectional"))
    )
    (net (code "131") (name "unconnected-(CON2-P$40-Pad40)") (class "Default")
      (node (ref "CON2") (pin "40") (pinfunction "P$40_40") (pintype "bidirectional"))
    )
    (net (code "132") (name "unconnected-(CON2-P$51-Pad51)") (class "Default")
      (node (ref "CON2") (pin "51") (pinfunction "P$51_51") (pintype "bidirectional"))
    )
    (net (code "133") (name "unconnected-(CON2-P$52-Pad52)") (class "Default")
      (node (ref "CON2") (pin "52") (pinfunction "P$52_52") (pintype "bidirectional"))
    )
    (net (code "134") (name "unconnected-(U5-DNC-Pad3)") (class "Default")
      (node (ref "U5") (pin "3") (pinfunction "DNC_3") (pintype "no_connect"))
    )
    (net (code "135") (name "unconnected-(U5-DNC-Pad5)") (class "Default")
      (node (ref "U5") (pin "5") (pinfunction "DNC_5") (pintype "no_connect"))
    )
    (net (code "136") (name "unconnected-(U5-DNC-Pad10)") (class "Default")
      (node (ref "U5") (pin "10") (pinfunction "DNC_10") (pintype "no_connect"))
    )
    (net (code "137") (name "unconnected-(U5-FACTORY-Pad9)") (class "Default")
      (node (ref "U5") (pin "9") (pinfunction "FACTORY_9") (pintype "no_connect"))
    )
    (net (code "138") (name "unconnected-(U5-P0.02{slash}AIN3-Pad24)") (class "Default")
      (node (ref "U5") (pin "24") (pinfunction "P0.02/AIN3_24") (pintype "bidirectional"))
    )
    (net (code "139") (name "unconnected-(U5-P0.03{slash}AIN4-Pad22)") (class "Default")
      (node (ref "U5") (pin "22") (pinfunction "P0.03/AIN4_22") (pintype "bidirectional"))
    )
    (net (code "140") (name "unconnected-(U5-P0.04{slash}AIN5-Pad32)") (class "Default")
      (node (ref "U5") (pin "32") (pinfunction "P0.04/AIN5_32") (pintype "bidirectional"))
    )
    (net (code "141") (name "unconnected-(U5-P0.05{slash}AIN6-Pad21)") (class "Default")
      (node (ref "U5") (pin "21") (pinfunction "P0.05/AIN6_21") (pintype "bidirectional"))
    )
    (net (code "142") (name "unconnected-(U5-P0.06{slash}AREF1{slash}AIN7-Pad31)") (class "Default")
      (node (ref "U5") (pin "31") (pinfunction "P0.06/AREF1/AIN7_31") (pintype "bidirectional"))
    )
    (net (code "143") (name "unconnected-(U5-P0.07-Pad26)") (class "Default")
      (node (ref "U5") (pin "26") (pinfunction "P0.07_26") (pintype "bidirectional"))
    )
    (net (code "144") (name "unconnected-(U5-P0.10-Pad27)") (class "Default")
      (node (ref "U5") (pin "27") (pinfunction "P0.10_27") (pintype "bidirectional"))
    )
    (net (code "145") (name "unconnected-(U5-P0.11-Pad17)") (class "Default")
      (node (ref "U5") (pin "17") (pinfunction "P0.11_17") (pintype "bidirectional"))
    )
    (net (code "146") (name "unconnected-(U5-P0.16-Pad14)") (class "Default")
      (node (ref "U5") (pin "14") (pinfunction "P0.16_14") (pintype "bidirectional"))
    )
    (net (code "147") (name "unconnected-(U5-P0.17-Pad12)") (class "Default")
      (node (ref "U5") (pin "12") (pinfunction "P0.17_12") (pintype "bidirectional"))
    )
    (net (code "148") (name "unconnected-(U5-P0.18-Pad13)") (class "Default")
      (node (ref "U5") (pin "13") (pinfunction "P0.18_13") (pintype "bidirectional"))
    )
  )
)
